# BluetoothSchematic.net
KiCad netlist of a schematic drawn in Altium Designer
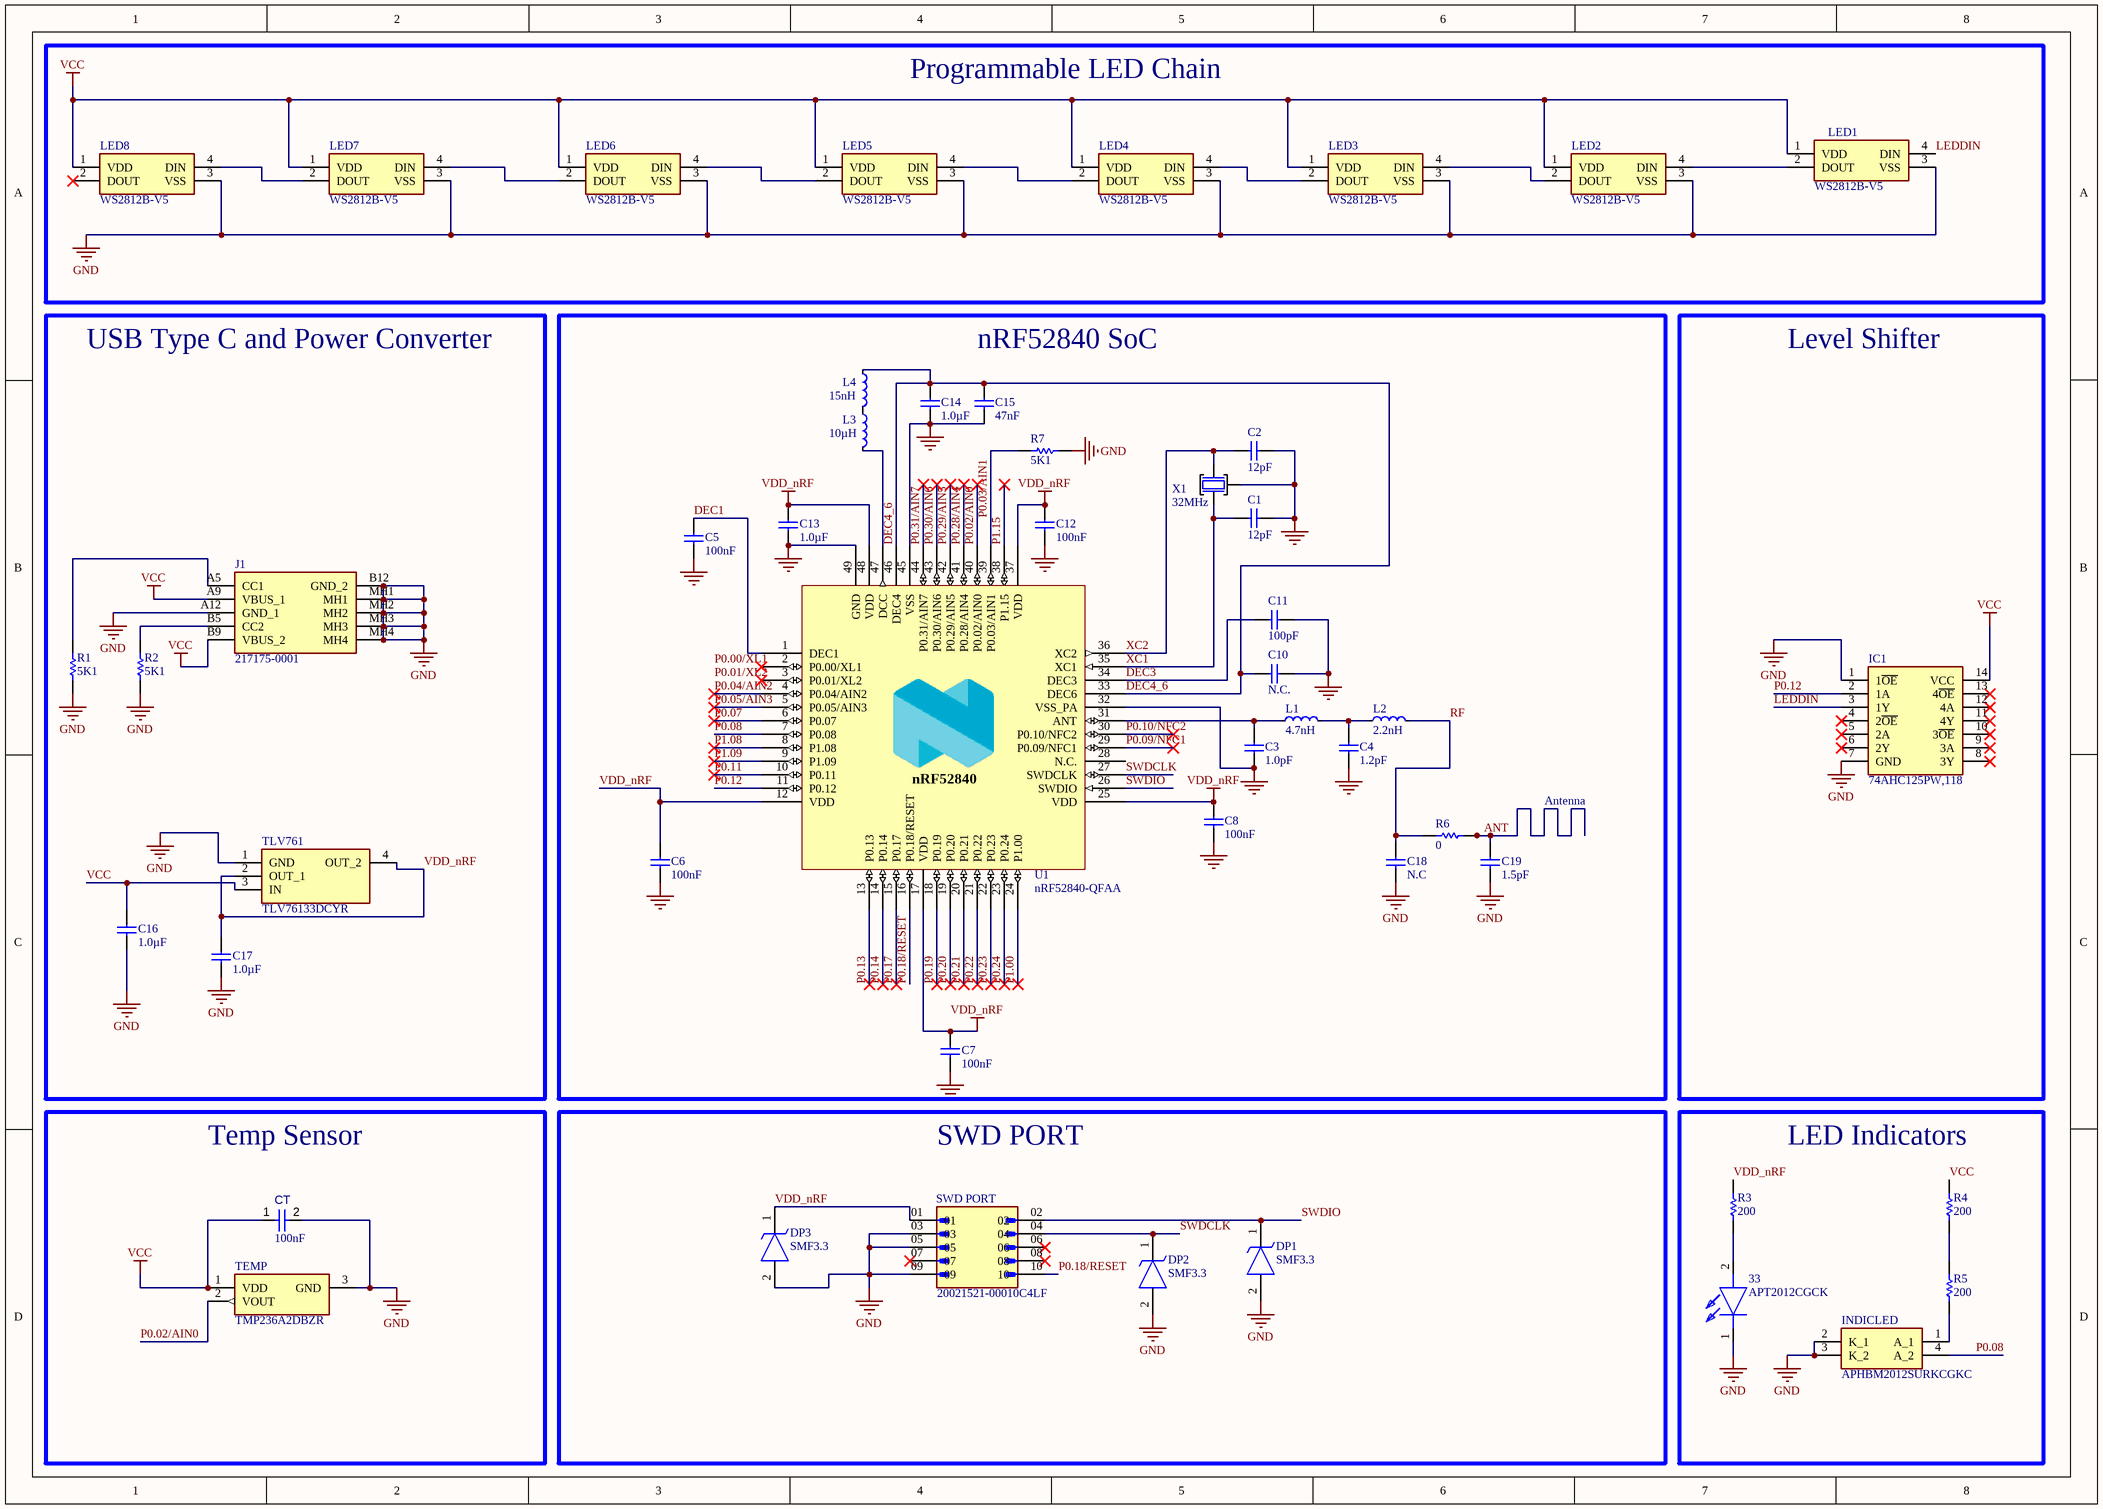
[diagram p0: BluetoothSchematic.SchDoc]

(export (version "E")
  (design (tool "Eeschema 10.0.6"))
  (components
    (comp (ref "33")
      (value "APT2012CGCK")
      (footprint "SamacSys:LEDC2012X50N")
      (description "LED")
      (fields (field (name "MOUSER PART NUMBER") "604-APT2012CGCK"))
      (libsource (lib "*") (part "APT2012CGCK"))
    )
    (comp (ref "C1")
      (value "12pF")
      (footprint "nrf52840_qfaa:CAPC0603X03L_C")
      (description "Capacitor, NP0, ±2%")
      (fields (field (name "PART NUMBER") "C0201-12p"))
      (libsource (lib "AltiumLib") (part "CAP"))
    )
    (comp (ref "C2")
      (value "12pF")
      (footprint "nrf52840_qfaa:CAPC0603X03L_C")
      (description "Capacitor, NP0, ±2%")
      (fields (field (name "PART NUMBER") "C0201-12p"))
      (libsource (lib "AltiumLib") (part "CAP"))
    )
    (comp (ref "C3")
      (value "1.0pF")
      (footprint "nrf52840_qfaa:CAPC0603X03L_C")
      (description "Capacitor, NP0, ±10%")
      (fields (field (name "PART NUMBER") "C0201-1.0p"))
      (libsource (lib "AltiumLib") (part "CAP"))
    )
    (comp (ref "C4")
      (value "1.2pF")
      (footprint "nrf52840_qfaa:CAPC0603X03L_C")
      (description "Capacitor, NP0, ±10%")
      (fields (field (name "PART NUMBER") "C0201-1.2p"))
      (libsource (lib "AltiumLib") (part "CAP"))
    )
    (comp (ref "C5")
      (value "100nF")
      (footprint "nrf52840_qfaa:CAPC0603X03L_C")
      (description "Capacitor, X5R, ±10%")
      (fields (field (name "PART NUMBER") "C0201-100n"))
      (libsource (lib "AltiumLib") (part "CAP"))
    )
    (comp (ref "C6")
      (value "100nF")
      (footprint "nrf52840_qfaa:CAPC0603X03L_C")
      (description "Capacitor, X5R, ±10%")
      (fields (field (name "PART NUMBER") "C0201-100n"))
      (libsource (lib "AltiumLib") (part "CAP"))
    )
    (comp (ref "C7")
      (value "100nF")
      (footprint "nrf52840_qfaa:CAPC0603X03L_C")
      (description "Capacitor, X5R, ±10%")
      (fields (field (name "PART NUMBER") "C0201-100n"))
      (libsource (lib "AltiumLib") (part "CAP"))
    )
    (comp (ref "C8")
      (value "100nF")
      (footprint "nrf52840_qfaa:CAPC0603X03L_C")
      (description "Capacitor, X5R, ±10%")
      (fields (field (name "PART NUMBER") "C0201-100n"))
      (libsource (lib "AltiumLib") (part "CAP"))
    )
    (comp (ref "C10")
      (value "N.C.")
      (footprint "nrf52840_qfaa:CAPC0603X03L_C_NC")
      (description "Not mounted")
      (fields (field (name "PART NUMBER") "C0201-N.C."))
      (libsource (lib "AltiumLib") (part "CAP"))
    )
    (comp (ref "C11")
      (value "100pF")
      (footprint "nrf52840_qfaa:CAPC0603X03L_C")
      (description "Capacitor, NP0, ±5%")
      (fields (field (name "PART NUMBER") "C0201-100p"))
      (libsource (lib "AltiumLib") (part "CAP"))
    )
    (comp (ref "C12")
      (value "100nF")
      (footprint "CAPC0603X03L_C")
      (description "Capacitor, X5R, ±10%")
      (fields (field (name "PART NUMBER") "C0201-100n"))
      (libsource (lib "AltiumLib") (part "CAP"))
    )
    (comp (ref "C13")
      (value "1.0µF")
      (footprint "nrf52840_qfaa:CAPC1005X04L")
      (description "Capacitor, X5R, ±10%")
      (fields (field (name "PART NUMBER") "C0402-1µ0"))
      (libsource (lib "AltiumLib") (part "CAP"))
    )
    (comp (ref "C14")
      (value "1.0µF")
      (footprint "nrf52840_qfaa:CAPC1005X04L")
      (description "Capacitor, X5R, ±10%")
      (fields (field (name "PART NUMBER") "C0402-1µ0"))
      (libsource (lib "AltiumLib") (part "CAP"))
    )
    (comp (ref "C15")
      (value "47nF")
      (footprint "nrf52840_qfaa:CAPC0603X03L_C")
      (description "Capacitor, X5R, ±10%")
      (fields (field (name "PART NUMBER") "C0201-47n"))
      (libsource (lib "AltiumLib") (part "CAP"))
    )
    (comp (ref "C16")
      (value "1.0µF")
      (footprint "nrf52840_qfaa:CAPC1005X04L")
      (description "Capacitor, X5R, ±10%")
      (fields (field (name "PART NUMBER") "C0402-1µ0"))
      (libsource (lib "AltiumLib") (part "CAP"))
    )
    (comp (ref "C17")
      (value "1.0µF")
      (footprint "nrf52840_qfaa:CAPC1005X04L")
      (description "Capacitor, X5R, ±10%")
      (fields (field (name "PART NUMBER") "C0402-1µ0"))
      (libsource (lib "AltiumLib") (part "CAP"))
    )
    (comp (ref "C18")
      (value "N.C")
      (footprint "nrf52840_qfaa:CAPC0603X03L_C")
      (description "Capacitor, NP0, ±10%")
      (fields (field (name "PART NUMBER") "C0201-1.2p"))
      (libsource (lib "AltiumLib") (part "CAP"))
    )
    (comp (ref "C19")
      (value "1.5pF")
      (footprint "nrf52840_qfaa:CAPC0603X03L_C")
      (description "Capacitor, NP0, ±10%")
      (fields (field (name "PART NUMBER") "C0201-1.2p"))
      (libsource (lib "AltiumLib") (part "CAP"))
    )
    (comp (ref "CT")
      (value "100nF")
      (footprint "CAPC1608X90X40NL10T20")
      (description "Chip Capacitor, 100 nF, +/- 10%, 50 V, 0603 (1608 Metric)")
      (fields (field (name "TOLERANCE") "10%") (field (name "Comment") "Capacitor 100 nF +/-10% 50 V 0603"))
      (libsource (lib "T Gosman") (part "CAP-NP-2"))
    )
    (comp (ref "DP1")
      (value "SMF3.3")
      (footprint "SamacSys:SOD3718X108N")
      (description "TVS Diode (Uni-directional)")
      (fields (field (name "MOUSER PART NUMBER") "576-SMF3.3"))
      (libsource (lib "*") (part "SMF3.3"))
    )
    (comp (ref "DP2")
      (value "SMF3.3")
      (footprint "SamacSys:SOD3718X108N")
      (description "TVS Diode (Uni-directional)")
      (fields (field (name "MOUSER PART NUMBER") "576-SMF3.3"))
      (libsource (lib "*") (part "SMF3.3"))
    )
    (comp (ref "DP3")
      (value "SMF3.3")
      (footprint "SamacSys:SOD3718X108N")
      (description "TVS Diode (Uni-directional)")
      (fields (field (name "MOUSER PART NUMBER") "576-SMF3.3"))
      (libsource (lib "*") (part "SMF3.3"))
    )
    (comp (ref "IC1")
      (value "74AHC125PW,118")
      (footprint "SamacSys:SOP65P640X110-14N")
      (description "Integrated Circuit")
      (fields (field (name "MOUSER PART NUMBER") "771-AHC125PW118"))
      (libsource (lib "*") (part "74AHC125PW,118"))
    )
    (comp (ref "INDICLED")
      (value "APHBM2012SURKCGKC")
      (footprint "SamacSys:APHBM2012SURKCGKC")
      (description "LED")
      (fields (field (name "MOUSER PART NUMBER") "604-BM2012SURKCGKC"))
      (libsource (lib "*") (part "APHBM2012SURKCGKC"))
    )
    (comp (ref "J1")
      (value "217175-0001")
      (footprint "SamacSys:2171750001")
      (description "Connector")
      (fields (field (name "MOUSER PART NUMBER") "538-217175-0001"))
      (libsource (lib "*") (part "217175-0001"))
    )
    (comp (ref "L1")
      (value "4.7nH")
      (footprint "nrf52840_qfaa:INDC0603X03L_C")
      (description "High frequency chip inductor ±5%")
      (fields (field (name "PART NUMBER") "L0201-4n7"))
      (libsource (lib "AltiumLib") (part "IND"))
    )
    (comp (ref "L2")
      (value "2.2nH")
      (footprint "nrf52840_qfaa:INDC0603X03L_C")
      (description "High frequency chip inductor ±5%")
      (fields (field (name "PART NUMBER") "L0201-2n2"))
      (libsource (lib "AltiumLib") (part "IND"))
    )
    (comp (ref "L3")
      (value "10µH")
      (footprint "nrf52840_qfaa:INDC1608X06L")
      (description "Chip inductor, IDC,min = 50 mA, ±20%")
      (fields (field (name "PART NUMBER") "L0603-10µ-TDK"))
      (libsource (lib "AltiumLib") (part "IND"))
    )
    (comp (ref "L4")
      (value "15nH")
      (footprint "nrf52840_qfaa:INDC1005X04L")
      (description "High frequency chip inductor ±10%")
      (fields (field (name "PART NUMBER") "L0402-15n"))
      (libsource (lib "AltiumLib") (part "IND"))
    )
    (comp (ref "LED1")
      (value "WS2812B-V5")
      (footprint "SamacSys:WS2812BV5")
      (description "LED")
      (libsource (lib "*") (part "WS2812B-V5"))
    )
    (comp (ref "LED2")
      (value "WS2812B-V5")
      (footprint "SamacSys:WS2812BV5")
      (description "LED")
      (libsource (lib "*") (part "WS2812B-V5"))
    )
    (comp (ref "LED3")
      (value "WS2812B-V5")
      (footprint "SamacSys:WS2812BV5")
      (description "LED")
      (libsource (lib "*") (part "WS2812B-V5"))
    )
    (comp (ref "LED4")
      (value "WS2812B-V5")
      (footprint "SamacSys:WS2812BV5")
      (description "LED")
      (libsource (lib "*") (part "WS2812B-V5"))
    )
    (comp (ref "LED5")
      (value "WS2812B-V5")
      (footprint "SamacSys:WS2812BV5")
      (description "LED")
      (libsource (lib "*") (part "WS2812B-V5"))
    )
    (comp (ref "LED6")
      (value "WS2812B-V5")
      (footprint "SamacSys:WS2812BV5")
      (description "LED")
      (libsource (lib "*") (part "WS2812B-V5"))
    )
    (comp (ref "LED7")
      (value "WS2812B-V5")
      (footprint "SamacSys:WS2812BV5")
      (description "LED")
      (libsource (lib "*") (part "WS2812B-V5"))
    )
    (comp (ref "LED8")
      (value "WS2812B-V5")
      (footprint "SamacSys:WS2812BV5")
      (description "LED")
      (libsource (lib "*") (part "WS2812B-V5"))
    )
    (comp (ref "R1")
      (value "5K1")
      (footprint "RESC3116X70X50ML13T20")
      (description "Chip Resistor, 0 Ohm, 0.25 W, -55 to 155 degC, 1206 (3216 Metric)")
      (fields (field (name "TOLERANCE") "0.05%") (field (name "POWER") "250mW"))
      (libsource (lib "T Gosman") (part "RES-2"))
    )
    (comp (ref "R2")
      (value "5K1")
      (footprint "RESC3116X70X50ML13T20")
      (description "Chip Resistor, 0 Ohm, 0.25 W, -55 to 155 degC, 1206 (3216 Metric)")
      (fields (field (name "TOLERANCE") "0.05%") (field (name "POWER") "250mW"))
      (libsource (lib "T Gosman") (part "RES-2"))
    )
    (comp (ref "R3")
      (value "200")
      (footprint "RESC3116X70X50ML13T20")
      (description "Chip Resistor, 0 Ohm, 0.25 W, -55 to 155 degC, 1206 (3216 Metric)")
      (fields (field (name "TOLERANCE") "0.05%") (field (name "POWER") "250mW"))
      (libsource (lib "T Gosman") (part "RES-2"))
    )
    (comp (ref "R4")
      (value "200")
      (footprint "RESC3116X70X50ML13T20")
      (description "Chip Resistor, 0 Ohm, 0.25 W, -55 to 155 degC, 1206 (3216 Metric)")
      (fields (field (name "TOLERANCE") "0.05%") (field (name "POWER") "250mW"))
      (libsource (lib "T Gosman") (part "RES-2"))
    )
    (comp (ref "R5")
      (value "200")
      (footprint "RESC3116X70X50ML13T20")
      (description "Chip Resistor, 0 Ohm, 0.25 W, -55 to 155 degC, 1206 (3216 Metric)")
      (fields (field (name "TOLERANCE") "0.05%") (field (name "POWER") "250mW"))
      (libsource (lib "T Gosman") (part "RES-2"))
    )
    (comp (ref "R6")
      (value "0")
      (footprint "RESC1608X55X25ML10T15")
      (description "Chip Resistor, 0 Ohm, 0.1 W, -55 to 155 degC, 0603 (1608 Metric)")
      (fields (field (name "POWER") "100mW") (field (name "TOLERANCE") "5%"))
      (libsource (lib "T Gosman") (part "RES-2"))
    )
    (comp (ref "R7")
      (value "5K1")
      (footprint "RESC3116X70X50ML13T20")
      (description "Chip Resistor, 0 Ohm, 0.25 W, -55 to 155 degC, 1206 (3216 Metric)")
      (fields (field (name "TOLERANCE") "0.05%") (field (name "POWER") "250mW"))
      (libsource (lib "T Gosman") (part "RES-2"))
    )
    (comp (ref "SWD PORT")
      (value "20021521-00010C4LF")
      (footprint "AMPHENOL_20021521-00010C4LF")
      (description "Minitek127Â®, Shrouded Board to Board Header, Surface Mount, 10 positions, 1.27mm (0.500in) pitch.")
      (fields (field (name "MF") "AMPHENOL ICC / FCI") (field (name "DIGI-KEY_PART_NUMBER") "609-6445-2-ND"))
      (libsource (lib "T Gosman") (part "20021521-00010C4LF"))
    )
    (comp (ref "TEMP")
      (value "TMP236A2DBZR")
      (footprint "SamacSys:SOT95P237X112-3N")
      (description "Undefined or Miscellaneous")
      (fields (field (name "MOUSER PART NUMBER") "595-TMP236A2DBZR"))
      (libsource (lib "*") (part "TMP236A2DBZR"))
    )
    (comp (ref "TLV761")
      (value "TLV76133DCYR")
      (footprint "SamacSys:SOT230P700X180-4N")
      (description "Integrated Circuit")
      (fields (field (name "MOUSER PART NUMBER") "595-TLV76133DCYR"))
      (libsource (lib "*") (part "TLV76133DCYR"))
    )
    (comp (ref "U1")
      (value "nRF52840-QFAA")
      (footprint "nrf52840_qfaa:QFN40P600X600X90-48N")
      (description "Multi-protocol Bluetooth Low Energy, IEEE 802.15.4, ANT and 2.4GHz proprietary system-on-chip")
      (libsource (lib "AltiumLib") (part "nRF52840_QFAA"))
    )
    (comp (ref "X1")
      (value "32MHz")
      (footprint "nrf52840_qfaa:XTAL_2016_NT")
      (description "XTAL SMD 2016, 32MHz, Cl=8pF, Total Tol: ±30ppm")
      (fields (field (name "PART NUMBER") "XTAL_SMD2016_32MHz_8pF_General_NT"))
      (libsource (lib "AltiumLib") (part "XTAL_4-pin_NT"))
    )
  )
  (nets
    (net (code "1") (name "/ANT") (class "Default")
      (node (ref "C19") (pin "2") (pinfunction "2_2") (pintype "passive"))
      (node (ref "R6") (pin "2") (pinfunction "2_2") (pintype "passive"))
    )
    (net (code "2") (name "/DEC1") (class "Default")
      (node (ref "C5") (pin "1") (pinfunction "1_1") (pintype "passive"))
      (node (ref "U1") (pin "1") (pinfunction "DEC1_1") (pintype "power_in"))
    )
    (net (code "3") (name "/DEC3") (class "Default")
      (node (ref "C11") (pin "1") (pinfunction "1_1") (pintype "passive"))
      (node (ref "U1") (pin "34") (pinfunction "DEC3_34") (pintype "power_in"))
    )
    (net (code "4") (name "/DEC4_6") (class "Default")
      (node (ref "C10") (pin "2") (pinfunction "2_2") (pintype "passive"))
      (node (ref "C14") (pin "2") (pinfunction "2_2") (pintype "passive"))
      (node (ref "C15") (pin "1") (pinfunction "1_1") (pintype "passive"))
      (node (ref "L4") (pin "1") (pinfunction "1_1") (pintype "passive"))
      (node (ref "U1") (pin "33") (pinfunction "DEC6_33") (pintype "power_in"))
      (node (ref "U1") (pin "46") (pinfunction "DEC4_46") (pintype "power_in"))
    )
    (net (code "5") (name "/LEDDIN") (class "Default")
      (node (ref "IC1") (pin "3") (pinfunction "1Y_3") (pintype "passive"))
      (node (ref "LED1") (pin "4") (pinfunction "DIN_4") (pintype "passive"))
    )
    (net (code "8") (name "/P0.02{slash}AIN0") (class "Default")
      (node (ref "TEMP") (pin "2") (pinfunction "VOUT_2") (pintype "output"))
      (node (ref "U1") (pin "40") (pinfunction "P0.02/AIN0_40") (pintype "bidirectional"))
    )
    (net (code "9") (name "/P0.03{slash}AIN1") (class "Default")
      (node (ref "R7") (pin "1") (pinfunction "1_1") (pintype "passive"))
      (node (ref "U1") (pin "39") (pinfunction "P0.03/AIN1_39") (pintype "bidirectional"))
    )
    (net (code "10") (name "/P0.04{slash}AIN2") (class "Default")
      (node (ref "U1") (pin "4") (pinfunction "P0.04/AIN2_4") (pintype "bidirectional+no_connect"))
    )
    (net (code "11") (name "/P0.05{slash}AIN3") (class "Default")
      (node (ref "U1") (pin "5") (pinfunction "P0.05/AIN3_5") (pintype "bidirectional+no_connect"))
    )
    (net (code "12") (name "/P0.07") (class "Default")
      (node (ref "U1") (pin "6") (pinfunction "P0.07_6") (pintype "bidirectional+no_connect"))
    )
    (net (code "13") (name "/P0.08") (class "Default")
      (node (ref "INDICLED") (pin "4") (pinfunction "A_2_4") (pintype "passive"))
      (node (ref "U1") (pin "7") (pinfunction "P0.08_7") (pintype "bidirectional"))
    )
    (net (code "14") (name "/P0.09{slash}NFC1") (class "Default")
      (node (ref "U1") (pin "29") (pinfunction "P0.09/NFC1_29") (pintype "bidirectional+no_connect"))
    )
    (net (code "15") (name "/P0.10{slash}NFC2") (class "Default")
      (node (ref "U1") (pin "30") (pinfunction "P0.10/NFC2_30") (pintype "bidirectional+no_connect"))
    )
    (net (code "16") (name "/P0.11") (class "Default")
      (node (ref "U1") (pin "10") (pinfunction "P0.11_10") (pintype "bidirectional+no_connect"))
    )
    (net (code "17") (name "/P0.12") (class "Default")
      (node (ref "IC1") (pin "2") (pinfunction "1A_2") (pintype "passive"))
      (node (ref "U1") (pin "11") (pinfunction "P0.12_11") (pintype "bidirectional"))
    )
    (net (code "18") (name "/P0.13") (class "Default")
      (node (ref "U1") (pin "13") (pinfunction "P0.13_13") (pintype "bidirectional+no_connect"))
    )
    (net (code "19") (name "/P0.14") (class "Default")
      (node (ref "U1") (pin "14") (pinfunction "P0.14_14") (pintype "bidirectional+no_connect"))
    )
    (net (code "20") (name "/P0.17") (class "Default")
      (node (ref "U1") (pin "15") (pinfunction "P0.17_15") (pintype "bidirectional+no_connect"))
    )
    (net (code "21") (name "/P0.18{slash}RESET") (class "Default")
      (node (ref "SWD PORT") (pin "10") (pinfunction "10_10") (pintype "passive"))
      (node (ref "U1") (pin "16") (pinfunction "P0.18/RESET_16") (pintype "bidirectional"))
    )
    (net (code "22") (name "/P0.19") (class "Default")
      (node (ref "U1") (pin "18") (pinfunction "P0.19_18") (pintype "bidirectional+no_connect"))
    )
    (net (code "23") (name "/P0.20") (class "Default")
      (node (ref "U1") (pin "19") (pinfunction "P0.20_19") (pintype "bidirectional+no_connect"))
    )
    (net (code "24") (name "/P0.21") (class "Default")
      (node (ref "U1") (pin "20") (pinfunction "P0.21_20") (pintype "bidirectional+no_connect"))
    )
    (net (code "25") (name "/P0.22") (class "Default")
      (node (ref "U1") (pin "21") (pinfunction "P0.22_21") (pintype "bidirectional+no_connect"))
    )
    (net (code "26") (name "/P0.23") (class "Default")
      (node (ref "U1") (pin "22") (pinfunction "P0.23_22") (pintype "bidirectional+no_connect"))
    )
    (net (code "27") (name "/P0.24") (class "Default")
      (node (ref "U1") (pin "23") (pinfunction "P0.24_23") (pintype "bidirectional+no_connect"))
    )
    (net (code "28") (name "/P0.28{slash}AIN4") (class "Default")
      (node (ref "U1") (pin "41") (pinfunction "P0.28/AIN4_41") (pintype "bidirectional+no_connect"))
    )
    (net (code "29") (name "/P0.29{slash}AIN5") (class "Default")
      (node (ref "U1") (pin "42") (pinfunction "P0.29/AIN5_42") (pintype "bidirectional+no_connect"))
    )
    (net (code "30") (name "/P0.30{slash}AIN6") (class "Default")
      (node (ref "U1") (pin "43") (pinfunction "P0.30/AIN6_43") (pintype "bidirectional+no_connect"))
    )
    (net (code "31") (name "/P0.31{slash}AIN7") (class "Default")
      (node (ref "U1") (pin "44") (pinfunction "P0.31/AIN7_44") (pintype "bidirectional+no_connect"))
    )
    (net (code "32") (name "/P1.00") (class "Default")
      (node (ref "U1") (pin "24") (pinfunction "P1.00_24") (pintype "bidirectional+no_connect"))
    )
    (net (code "33") (name "/P1.08") (class "Default")
      (node (ref "U1") (pin "8") (pinfunction "P1.08_8") (pintype "bidirectional+no_connect"))
    )
    (net (code "34") (name "/P1.09") (class "Default")
      (node (ref "U1") (pin "9") (pinfunction "P1.09_9") (pintype "bidirectional+no_connect"))
    )
    (net (code "35") (name "/P1.15") (class "Default")
      (node (ref "U1") (pin "38") (pinfunction "P1.15_38") (pintype "bidirectional+no_connect"))
    )
    (net (code "36") (name "/RF") (class "Default")
      (node (ref "C18") (pin "2") (pinfunction "2_2") (pintype "passive"))
      (node (ref "L2") (pin "2") (pinfunction "2_2") (pintype "passive"))
      (node (ref "R6") (pin "1") (pinfunction "1_1") (pintype "passive"))
    )
    (net (code "37") (name "/SWDCLK") (class "Default")
      (node (ref "DP2") (pin "1") (pinfunction "K_1") (pintype "passive"))
      (node (ref "SWD PORT") (pin "04") (pinfunction "04_04") (pintype "passive"))
      (node (ref "U1") (pin "27") (pinfunction "SWDCLK_27") (pintype "bidirectional"))
    )
    (net (code "38") (name "/SWDIO") (class "Default")
      (node (ref "DP1") (pin "1") (pinfunction "K_1") (pintype "passive"))
      (node (ref "SWD PORT") (pin "02") (pinfunction "02_02") (pintype "passive"))
      (node (ref "U1") (pin "26") (pinfunction "SWDIO_26") (pintype "input"))
    )
    (net (code "39") (name "/XC1") (class "Default")
      (node (ref "C1") (pin "1") (pinfunction "1_1") (pintype "passive"))
      (node (ref "U1") (pin "35") (pinfunction "XC1_35") (pintype "input"))
      (node (ref "X1") (pin "1") (pinfunction "IN_1") (pintype "passive"))
    )
    (net (code "40") (name "/XC2") (class "Default")
      (node (ref "C2") (pin "1") (pinfunction "1_1") (pintype "passive"))
      (node (ref "U1") (pin "36") (pinfunction "XC2_36") (pintype "output"))
      (node (ref "X1") (pin "3") (pinfunction "OUT_3") (pintype "passive"))
    )
    (net (code "41") (name "GND") (class "Default")
      (node (ref "33") (pin "1") (pinfunction "K_1") (pintype "passive"))
      (node (ref "C1") (pin "2") (pinfunction "2_2") (pintype "passive"))
      (node (ref "C10") (pin "1") (pinfunction "1_1") (pintype "passive"))
      (node (ref "C11") (pin "2") (pinfunction "2_2") (pintype "passive"))
      (node (ref "C12") (pin "2") (pinfunction "2_2") (pintype "passive"))
      (node (ref "C13") (pin "2") (pinfunction "2_2") (pintype "passive"))
      (node (ref "C14") (pin "1") (pinfunction "1_1") (pintype "passive"))
      (node (ref "C15") (pin "2") (pinfunction "2_2") (pintype "passive"))
      (node (ref "C16") (pin "2") (pinfunction "2_2") (pintype "passive"))
      (node (ref "C17") (pin "2") (pinfunction "2_2") (pintype "passive"))
      (node (ref "C18") (pin "1") (pinfunction "1_1") (pintype "passive"))
      (node (ref "C19") (pin "1") (pinfunction "1_1") (pintype "passive"))
      (node (ref "C2") (pin "2") (pinfunction "2_2") (pintype "passive"))
      (node (ref "C3") (pin "1") (pinfunction "1_1") (pintype "passive"))
      (node (ref "C4") (pin "1") (pinfunction "1_1") (pintype "passive"))
      (node (ref "C5") (pin "2") (pinfunction "2_2") (pintype "passive"))
      (node (ref "C6") (pin "2") (pinfunction "2_2") (pintype "passive"))
      (node (ref "C7") (pin "2") (pinfunction "2_2") (pintype "passive"))
      (node (ref "C8") (pin "2") (pinfunction "2_2") (pintype "passive"))
      (node (ref "CT") (pin "2") (pinfunction "2_2") (pintype "passive"))
      (node (ref "DP1") (pin "2") (pinfunction "A_2") (pintype "passive"))
      (node (ref "DP2") (pin "2") (pinfunction "A_2") (pintype "passive"))
      (node (ref "DP3") (pin "2") (pinfunction "A_2") (pintype "passive"))
      (node (ref "IC1") (pin "1") (pinfunction "1~{OE}_1") (pintype "passive"))
      (node (ref "IC1") (pin "7") (pinfunction "GND_7") (pintype "passive"))
      (node (ref "INDICLED") (pin "2") (pinfunction "K_1_2") (pintype "passive"))
      (node (ref "INDICLED") (pin "3") (pinfunction "K_2_3") (pintype "passive"))
      (node (ref "J1") (pin "A12") (pinfunction "GND_1_A12") (pintype "passive"))
      (node (ref "J1") (pin "B12") (pinfunction "GND_2_B12") (pintype "passive"))
      (node (ref "J1") (pin "MH1") (pinfunction "MH1_MH1") (pintype "passive"))
      (node (ref "J1") (pin "MH2") (pinfunction "MH2_MH2") (pintype "passive"))
      (node (ref "J1") (pin "MH3") (pinfunction "MH3_MH3") (pintype "passive"))
      (node (ref "J1") (pin "MH4") (pinfunction "MH4_MH4") (pintype "passive"))
      (node (ref "LED1") (pin "3") (pinfunction "VSS_3") (pintype "passive"))
      (node (ref "LED2") (pin "3") (pinfunction "VSS_3") (pintype "passive"))
      (node (ref "LED3") (pin "3") (pinfunction "VSS_3") (pintype "passive"))
      (node (ref "LED4") (pin "3") (pinfunction "VSS_3") (pintype "passive"))
      (node (ref "LED5") (pin "3") (pinfunction "VSS_3") (pintype "passive"))
      (node (ref "LED6") (pin "3") (pinfunction "VSS_3") (pintype "passive"))
      (node (ref "LED7") (pin "3") (pinfunction "VSS_3") (pintype "passive"))
      (node (ref "LED8") (pin "3") (pinfunction "VSS_3") (pintype "passive"))
      (node (ref "R1") (pin "2") (pinfunction "2_2") (pintype "passive"))
      (node (ref "R2") (pin "2") (pinfunction "2_2") (pintype "passive"))
      (node (ref "R7") (pin "2") (pinfunction "2_2") (pintype "passive"))
      (node (ref "SWD PORT") (pin "03") (pinfunction "03_03") (pintype "passive"))
      (node (ref "SWD PORT") (pin "05") (pinfunction "05_05") (pintype "passive"))
      (node (ref "SWD PORT") (pin "09") (pinfunction "09_09") (pintype "passive"))
      (node (ref "TEMP") (pin "3") (pinfunction "GND_3") (pintype "power_in"))
      (node (ref "TLV761") (pin "1") (pinfunction "GND_1") (pintype "passive"))
      (node (ref "U1") (pin "32") (pinfunction "VSS_PA_32") (pintype "power_in"))
      (node (ref "U1") (pin "45") (pinfunction "VSS_45") (pintype "power_in"))
      (node (ref "U1") (pin "49") (pinfunction "GND_49") (pintype "power_in"))
      (node (ref "X1") (pin "2") (pinfunction "GND_2") (pintype "passive"))
    )
    (net (code "42") (name "Net-(33-A)") (class "Default")
      (node (ref "33") (pin "2") (pinfunction "A_2") (pintype "passive"))
      (node (ref "R3") (pin "2") (pinfunction "2_2") (pintype "passive"))
    )
    (net (code "43") (name "Net-(C4-Pad2)") (class "Default")
      (node (ref "C4") (pin "2") (pinfunction "2_2") (pintype "passive"))
      (node (ref "L1") (pin "2") (pinfunction "2_2") (pintype "passive"))
      (node (ref "L2") (pin "1") (pinfunction "1_1") (pintype "passive"))
    )
    (net (code "44") (name "Net-(INDICLED-A_1)") (class "Default")
      (node (ref "INDICLED") (pin "1") (pinfunction "A_1_1") (pintype "passive"))
      (node (ref "R5") (pin "2") (pinfunction "2_2") (pintype "passive"))
    )
    (net (code "45") (name "Net-(J1-CC1)") (class "Default")
      (node (ref "J1") (pin "A5") (pinfunction "CC1_A5") (pintype "passive"))
      (node (ref "R1") (pin "1") (pinfunction "1_1") (pintype "passive"))
    )
    (net (code "46") (name "Net-(J1-CC2)") (class "Default")
      (node (ref "J1") (pin "B5") (pinfunction "CC2_B5") (pintype "passive"))
      (node (ref "R2") (pin "1") (pinfunction "1_1") (pintype "passive"))
    )
    (net (code "47") (name "Net-(L3-Pad1)") (class "Default")
      (node (ref "L3") (pin "1") (pinfunction "1_1") (pintype "passive"))
      (node (ref "L4") (pin "2") (pinfunction "2_2") (pintype "passive"))
    )
    (net (code "48") (name "Net-(LED1-DOUT)") (class "Default")
      (node (ref "LED1") (pin "2") (pinfunction "DOUT_2") (pintype "passive"))
      (node (ref "LED2") (pin "4") (pinfunction "DIN_4") (pintype "passive"))
    )
    (net (code "49") (name "Net-(LED2-DOUT)") (class "Default")
      (node (ref "LED2") (pin "2") (pinfunction "DOUT_2") (pintype "passive"))
      (node (ref "LED3") (pin "4") (pinfunction "DIN_4") (pintype "passive"))
    )
    (net (code "50") (name "Net-(LED3-DOUT)") (class "Default")
      (node (ref "LED3") (pin "2") (pinfunction "DOUT_2") (pintype "passive"))
      (node (ref "LED4") (pin "4") (pinfunction "DIN_4") (pintype "passive"))
    )
    (net (code "51") (name "Net-(LED4-DOUT)") (class "Default")
      (node (ref "LED4") (pin "2") (pinfunction "DOUT_2") (pintype "passive"))
      (node (ref "LED5") (pin "4") (pinfunction "DIN_4") (pintype "passive"))
    )
    (net (code "52") (name "Net-(LED5-DOUT)") (class "Default")
      (node (ref "LED5") (pin "2") (pinfunction "DOUT_2") (pintype "passive"))
      (node (ref "LED6") (pin "4") (pinfunction "DIN_4") (pintype "passive"))
    )
    (net (code "53") (name "Net-(LED6-DOUT)") (class "Default")
      (node (ref "LED6") (pin "2") (pinfunction "DOUT_2") (pintype "passive"))
      (node (ref "LED7") (pin "4") (pinfunction "DIN_4") (pintype "passive"))
    )
    (net (code "54") (name "Net-(LED7-DOUT)") (class "Default")
      (node (ref "LED7") (pin "2") (pinfunction "DOUT_2") (pintype "passive"))
      (node (ref "LED8") (pin "4") (pinfunction "DIN_4") (pintype "passive"))
    )
    (net (code "55") (name "Net-(R4-Pad2)") (class "Default")
      (node (ref "R4") (pin "2") (pinfunction "2_2") (pintype "passive"))
      (node (ref "R5") (pin "1") (pinfunction "1_1") (pintype "passive"))
    )
    (net (code "56") (name "Net-(U1-ANT)") (class "Default")
      (node (ref "C3") (pin "2") (pinfunction "2_2") (pintype "passive"))
      (node (ref "L1") (pin "1") (pinfunction "1_1") (pintype "passive"))
      (node (ref "U1") (pin "31") (pinfunction "ANT_31") (pintype "bidirectional"))
    )
    (net (code "57") (name "Net-(U1-DCC)") (class "Default")
      (node (ref "L3") (pin "2") (pinfunction "2_2") (pintype "passive"))
      (node (ref "U1") (pin "47") (pinfunction "DCC_47") (pintype "output"))
    )
    (net (code "58") (name "VCC") (class "Default")
      (node (ref "C16") (pin "1") (pinfunction "1_1") (pintype "passive"))
      (node (ref "CT") (pin "1") (pinfunction "1_1") (pintype "passive"))
      (node (ref "IC1") (pin "14") (pinfunction "VCC_14") (pintype "passive"))
      (node (ref "J1") (pin "A9") (pinfunction "VBUS_1_A9") (pintype "passive"))
      (node (ref "J1") (pin "B9") (pinfunction "VBUS_2_B9") (pintype "passive"))
      (node (ref "LED1") (pin "1") (pinfunction "VDD_1") (pintype "passive"))
      (node (ref "LED2") (pin "1") (pinfunction "VDD_1") (pintype "passive"))
      (node (ref "LED3") (pin "1") (pinfunction "VDD_1") (pintype "passive"))
      (node (ref "LED4") (pin "1") (pinfunction "VDD_1") (pintype "passive"))
      (node (ref "LED5") (pin "1") (pinfunction "VDD_1") (pintype "passive"))
      (node (ref "LED6") (pin "1") (pinfunction "VDD_1") (pintype "passive"))
      (node (ref "LED7") (pin "1") (pinfunction "VDD_1") (pintype "passive"))
      (node (ref "LED8") (pin "1") (pinfunction "VDD_1") (pintype "passive"))
      (node (ref "R4") (pin "1") (pinfunction "1_1") (pintype "passive"))
      (node (ref "TEMP") (pin "1") (pinfunction "VDD_1") (pintype "power_in"))
      (node (ref "TLV761") (pin "3") (pinfunction "IN_3") (pintype "passive"))
    )
    (net (code "59") (name "VDD_nRF") (class "Default")
      (node (ref "C12") (pin "1") (pinfunction "1_1") (pintype "passive"))
      (node (ref "C13") (pin "1") (pinfunction "1_1") (pintype "passive"))
      (node (ref "C17") (pin "1") (pinfunction "1_1") (pintype "passive"))
      (node (ref "C6") (pin "1") (pinfunction "1_1") (pintype "passive"))
      (node (ref "C7") (pin "1") (pinfunction "1_1") (pintype "passive"))
      (node (ref "C8") (pin "1") (pinfunction "1_1") (pintype "passive"))
      (node (ref "DP3") (pin "1") (pinfunction "K_1") (pintype "passive"))
      (node (ref "R3") (pin "1") (pinfunction "1_1") (pintype "passive"))
      (node (ref "SWD PORT") (pin "01") (pinfunction "01_01") (pintype "passive"))
      (node (ref "TLV761") (pin "2") (pinfunction "OUT_1_2") (pintype "passive"))
      (node (ref "TLV761") (pin "4") (pinfunction "OUT_2_4") (pintype "passive"))
      (node (ref "U1") (pin "12") (pinfunction "VDD_12") (pintype "power_in"))
      (node (ref "U1") (pin "17") (pinfunction "VDD_17") (pintype "power_in"))
      (node (ref "U1") (pin "25") (pinfunction "VDD_25") (pintype "power_in"))
      (node (ref "U1") (pin "37") (pinfunction "VDD_37") (pintype "power_in"))
      (node (ref "U1") (pin "48") (pinfunction "VDD_48") (pintype "power_in"))
    )
    (net (code "60") (name "unconnected-(IC1-2A-Pad5)") (class "Default")
      (node (ref "IC1") (pin "5") (pinfunction "2A_5") (pintype "passive+no_connect"))
    )
    (net (code "61") (name "unconnected-(IC1-2Y-Pad6)") (class "Default")
      (node (ref "IC1") (pin "6") (pinfunction "2Y_6") (pintype "passive+no_connect"))
    )
    (net (code "62") (name "unconnected-(IC1-2~{OE}-Pad4)") (class "Default")
      (node (ref "IC1") (pin "4") (pinfunction "2~{OE}_4") (pintype "passive+no_connect"))
    )
    (net (code "63") (name "unconnected-(IC1-3A-Pad9)") (class "Default")
      (node (ref "IC1") (pin "9") (pinfunction "3A_9") (pintype "passive+no_connect"))
    )
    (net (code "64") (name "unconnected-(IC1-3Y-Pad8)") (class "Default")
      (node (ref "IC1") (pin "8") (pinfunction "3Y_8") (pintype "passive+no_connect"))
    )
    (net (code "65") (name "unconnected-(IC1-3~{OE}-Pad10)") (class "Default")
      (node (ref "IC1") (pin "10") (pinfunction "3~{OE}_10") (pintype "passive+no_connect"))
    )
    (net (code "66") (name "unconnected-(IC1-4A-Pad12)") (class "Default")
      (node (ref "IC1") (pin "12") (pinfunction "4A_12") (pintype "passive+no_connect"))
    )
    (net (code "67") (name "unconnected-(IC1-4Y-Pad11)") (class "Default")
      (node (ref "IC1") (pin "11") (pinfunction "4Y_11") (pintype "passive+no_connect"))
    )
    (net (code "68") (name "unconnected-(IC1-4~{OE}-Pad13)") (class "Default")
      (node (ref "IC1") (pin "13") (pinfunction "4~{OE}_13") (pintype "passive+no_connect"))
    )
    (net (code "69") (name "unconnected-(LED8-DOUT-Pad2)") (class "Default")
      (node (ref "LED8") (pin "2") (pinfunction "DOUT_2") (pintype "passive+no_connect"))
    )
    (net (code "70") (name "unconnected-(SWD PORT-Pad06)") (class "Default")
      (node (ref "SWD PORT") (pin "06") (pinfunction "06_06") (pintype "passive+no_connect"))
    )
    (net (code "71") (name "unconnected-(SWD PORT-Pad07)") (class "Default")
      (node (ref "SWD PORT") (pin "07") (pinfunction "07_07") (pintype "passive+no_connect"))
    )
    (net (code "72") (name "unconnected-(SWD PORT-Pad08)") (class "Default")
      (node (ref "SWD PORT") (pin "08") (pinfunction "08_08") (pintype "passive+no_connect"))
    )
    (net (code "73") (name "unconnected-(U1-N.C.-Pad28)") (class "Default")
      (node (ref "U1") (pin "28") (pinfunction "N.C._28") (pintype "passive"))
    )
    (net (code "74") (name "unconnected-(U1-P0.00{slash}XL1-Pad2)") (class "Default")
      (node (ref "U1") (pin "2") (pinfunction "P0.00/XL1_2") (pintype "bidirectional+no_connect"))
    )
    (net (code "75") (name "unconnected-(U1-P0.01{slash}XL2-Pad3)") (class "Default")
      (node (ref "U1") (pin "3") (pinfunction "P0.01/XL2_3") (pintype "bidirectional+no_connect"))
    )
  )
)
